# Hoja_Micro.net
KiCad netlist of a schematic drawn in Altium Designer
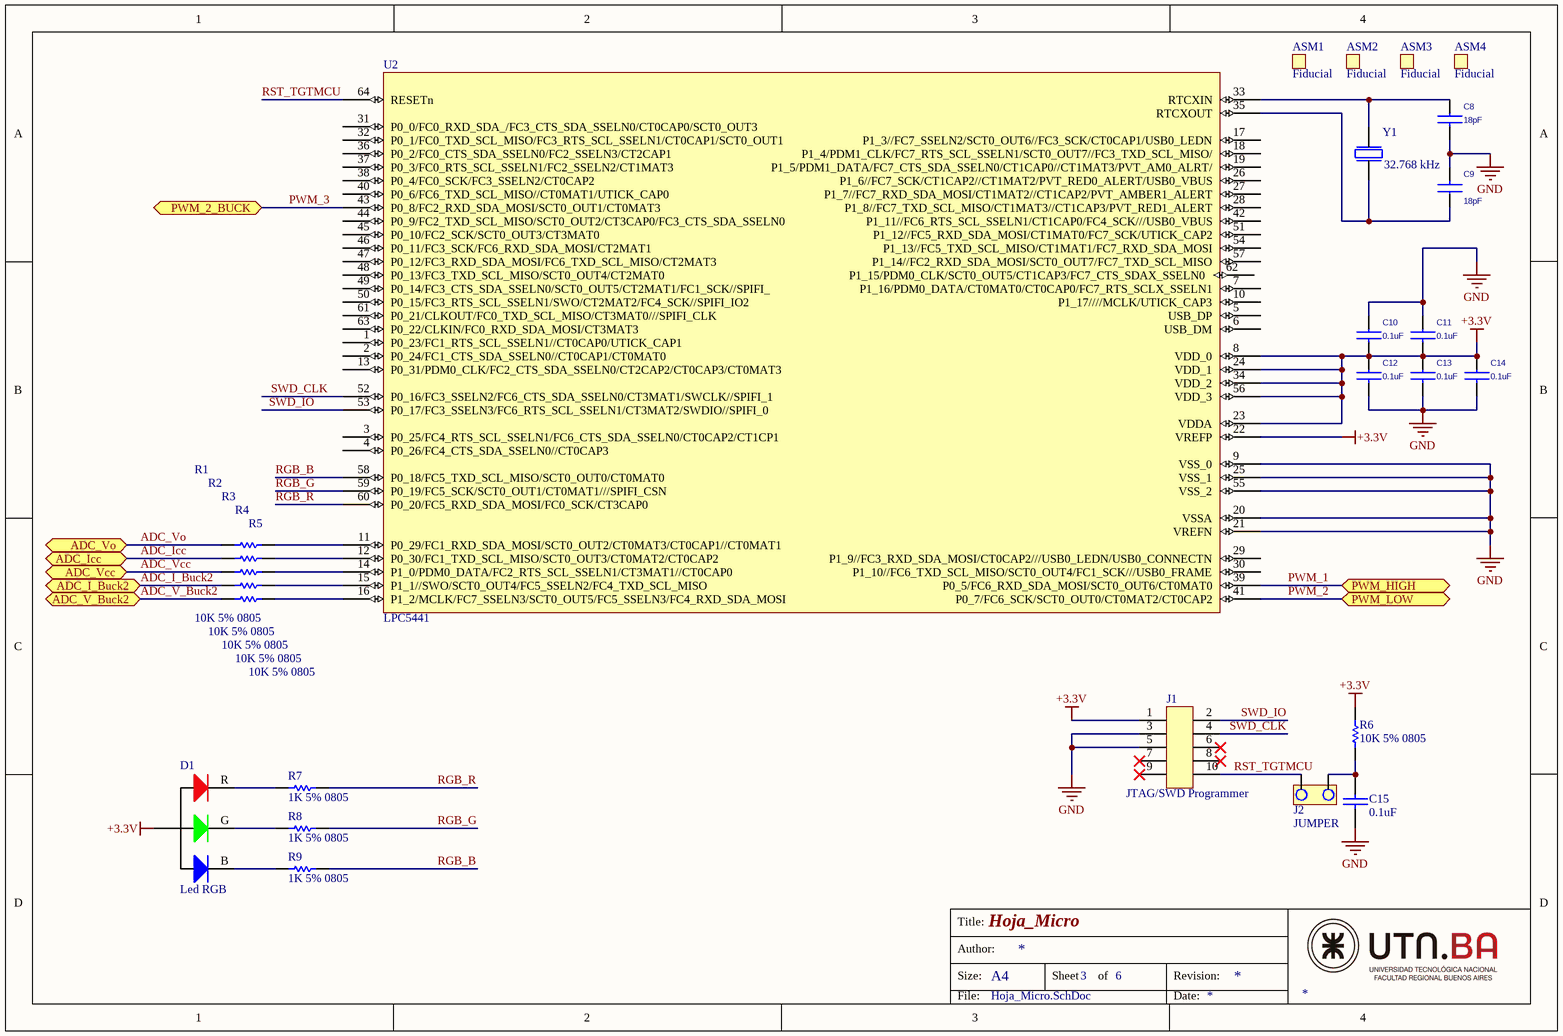
[diagram p0: Hoja_Micro.SchDoc]

(export (version "E")
  (design (tool "Eeschema 10.0.6"))
  (components
    (comp (ref "ASM1")
      (value "Fiducial")
      (footprint "Fiducial")
      (description "Fiducial Mark for PCB Asembly on Pick N' Place")
      (libsource (lib "Libreria_Casera") (part "Fiducial"))
    )
    (comp (ref "ASM2")
      (value "Fiducial")
      (footprint "Fiducial")
      (description "Fiducial Mark for PCB Asembly on Pick N' Place")
      (libsource (lib "Libreria_Casera") (part "Fiducial"))
    )
    (comp (ref "ASM3")
      (value "Fiducial")
      (footprint "Fiducial")
      (description "Fiducial Mark for PCB Asembly on Pick N' Place")
      (libsource (lib "Libreria_Casera") (part "Fiducial"))
    )
    (comp (ref "ASM4")
      (value "Fiducial")
      (footprint "Fiducial")
      (description "Fiducial Mark for PCB Asembly on Pick N' Place")
      (libsource (lib "Libreria_Casera") (part "Fiducial"))
    )
    (comp (ref "C8")
      (value "18pF")
      (footprint "0805")
      (description "CAP CER 0.1UF X7R 0805")
      (libsource (lib "*") (part "CAPACITOR NON-POL"))
    )
    (comp (ref "C9")
      (value "18pF")
      (footprint "0805")
      (description "CAP CER 0.1UF X7R 0805")
      (libsource (lib "*") (part "CAPACITOR NON-POL"))
    )
    (comp (ref "C10")
      (value "0.1uF")
      (footprint "0805")
      (description "CAP CER 0.1UF X7R 0805")
      (libsource (lib "*") (part "CAP NP"))
    )
    (comp (ref "C11")
      (value "0.1uF")
      (footprint "0805")
      (description "CAP CER 0.1UF X7R 0805")
      (libsource (lib "*") (part "CAP NP"))
    )
    (comp (ref "C12")
      (value "0.1uF")
      (footprint "0805")
      (description "CAP CER 0.1UF X7R 0805")
      (libsource (lib "*") (part "CAP NP"))
    )
    (comp (ref "C13")
      (value "0.1uF")
      (footprint "0805")
      (description "CAP CER 0.1UF X7R 0805")
      (libsource (lib "*") (part "CAP NP"))
    )
    (comp (ref "C14")
      (value "0.1uF")
      (footprint "0805")
      (description "CAP CER 0.1UF X7R 0805")
      (libsource (lib "*") (part "CAP NP"))
    )
    (comp (ref "C15")
      (value "0.1uF")
      (footprint "0805")
      (description "CAP CER 0.1UF X7R 0805")
      (libsource (lib "Libreria_Casera") (part "CAP"))
    )
    (comp (ref "D1")
      (value "Led RGB")
      (footprint "4-plcc")
      (description "CREE LED P/N: CLV1L-FKB-CHMMQEHBB7673673CT-ND\r\nCREE LED P/N: CLMVC-FKA-CL1D1L71BB7C3C3CT-ND")
      (libsource (lib "FRDM-KL46Z") (part "LED_RGB"))
    )
    (comp (ref "J1")
      (value "JTAG/SWD Programmer")
      (footprint "FTSH-105-01-XXX-DV-K")
      (description "CONN HEADER 10POS DUAL .05\" SMD -> FTSH-105-01-F-DV-K")
      (libsource (lib "FRDM-KL46Z") (part "JTAG"))
    )
    (comp (ref "J2") (value "JUMPER") (footprint "JUMPER2") (libsource (lib "LIBEBAL") (part "JUMPER")))
    (comp (ref "R1")
      (value "10K 5% 0805")
      (footprint "0805")
      (libsource (lib "Libreria_Casera") (part "RES"))
    )
    (comp (ref "R2")
      (value "10K 5% 0805")
      (footprint "0805")
      (libsource (lib "Libreria_Casera") (part "RES"))
    )
    (comp (ref "R3")
      (value "10K 5% 0805")
      (footprint "0805")
      (libsource (lib "Libreria_Casera") (part "RES"))
    )
    (comp (ref "R4")
      (value "10K 5% 0805")
      (footprint "0805")
      (libsource (lib "Libreria_Casera") (part "RES"))
    )
    (comp (ref "R5")
      (value "10K 5% 0805")
      (footprint "0805")
      (libsource (lib "Libreria_Casera") (part "RES"))
    )
    (comp (ref "R6")
      (value "10K 5% 0805")
      (footprint "0805")
      (description "RES SMD 10K OHM 5% 1/8W 0805")
      (libsource (lib "Libreria_Casera") (part "RES"))
    )
    (comp (ref "R7") (value "1K 5% 0805") (footprint "0805") (libsource (lib "Libreria_Casera") (part "RES")))
    (comp (ref "R8") (value "1K 5% 0805") (footprint "0805") (libsource (lib "Libreria_Casera") (part "RES")))
    (comp (ref "R9") (value "1K 5% 0805") (footprint "0805") (libsource (lib "Libreria_Casera") (part "RES")))
    (comp (ref "U2")
      (value "LPC5441")
      (footprint "LQFP64")
      (libsource (lib "Libreria_Casera") (part "LPC5441"))
    )
    (comp (ref "Y1")
      (value "32.768 kHz")
      (footprint "ABS07_Xtal")
      (description "XTAL ABS07 by ABRACON LLC")
      (libsource (lib "Libreria_Casera") (part "XTAL ABS07"))
    )
  )
  (nets
    (net (code "1") (name "+3.3V") (class "Default")
      (node (ref "C10") (pin "2") (pinfunction "2_2") (pintype "passive"))
      (node (ref "C11") (pin "2") (pinfunction "2_2") (pintype "passive"))
      (node (ref "C12") (pin "1") (pinfunction "1_1") (pintype "passive"))
      (node (ref "C13") (pin "1") (pinfunction "1_1") (pintype "passive"))
      (node (ref "C14") (pin "1") (pinfunction "1_1") (pintype "passive"))
      (node (ref "D1") (pin "A") (pinfunction "20_A") (pintype "passive"))
      (node (ref "J1") (pin "1") (pinfunction "36_1") (pintype "passive"))
      (node (ref "R6") (pin "2") (pinfunction "2_2") (pintype "passive"))
      (node (ref "U2") (pin "22") (pinfunction "VREFP_22") (pintype "bidirectional"))
      (node (ref "U2") (pin "23") (pinfunction "VDDA_23") (pintype "bidirectional"))
      (node (ref "U2") (pin "24") (pinfunction "VDD_1_24") (pintype "bidirectional"))
      (node (ref "U2") (pin "34") (pinfunction "VDD_2_34") (pintype "bidirectional"))
      (node (ref "U2") (pin "56") (pinfunction "VDD_3_56") (pintype "bidirectional"))
      (node (ref "U2") (pin "8") (pinfunction "VDD_0_8") (pintype "bidirectional"))
    )
    (net (code "2") (name "/ADC_I_Buck2") (class "Default")
      (node (ref "R4") (pin "2") (pinfunction "2_2") (pintype "passive"))
    )
    (net (code "3") (name "/ADC_Icc") (class "Default")
      (node (ref "R2") (pin "2") (pinfunction "2_2") (pintype "passive"))
    )
    (net (code "4") (name "/ADC_V_Buck2") (class "Default")
      (node (ref "R5") (pin "2") (pinfunction "2_2") (pintype "passive"))
    )
    (net (code "5") (name "/ADC_Vcc") (class "Default")
      (node (ref "R3") (pin "2") (pinfunction "2_2") (pintype "passive"))
    )
    (net (code "6") (name "/ADC_Vo") (class "Default")
      (node (ref "R1") (pin "2") (pinfunction "2_2") (pintype "passive"))
    )
    (net (code "7") (name "/PWM_1") (class "Default")
      (node (ref "U2") (pin "39") (pinfunction "P0_5/FC6_RXD_SDA_MOSI/SCT0_OUT6/CT0MAT0_39") (pintype "bidirectional"))
    )
    (net (code "8") (name "/PWM_2") (class "Default")
      (node (ref "U2") (pin "41") (pinfunction "P0_7/FC6_SCK/SCT0_OUT0/CT0MAT2/CT0CAP2_41") (pintype "bidirectional"))
    )
    (net (code "9") (name "/PWM_3") (class "Default")
      (node (ref "U2") (pin "43") (pinfunction "P0_8/FC2_RXD_SDA_MOSI/SCT0_OUT1/CT0MAT3_43") (pintype "bidirectional"))
    )
    (net (code "10") (name "/RGB_B") (class "Default")
      (node (ref "R9") (pin "1") (pinfunction "1_1") (pintype "passive"))
      (node (ref "U2") (pin "58") (pinfunction "P0_18/FC5_TXD_SCL_MISO/SCT0_OUT0/CT0MAT0_58") (pintype "bidirectional"))
    )
    (net (code "11") (name "/RGB_G") (class "Default")
      (node (ref "R8") (pin "1") (pinfunction "1_1") (pintype "passive"))
      (node (ref "U2") (pin "59") (pinfunction "P0_19/FC5_SCK/SCT0_OUT1/CT0MAT1///SPIFI_CSN_59") (pintype "bidirectional"))
    )
    (net (code "12") (name "/RGB_R") (class "Default")
      (node (ref "R7") (pin "1") (pinfunction "1_1") (pintype "passive"))
      (node (ref "U2") (pin "60") (pinfunction "P0_20/FC5_RXD_SDA_MOSI/FC0_SCK/CT3CAP0_60") (pintype "bidirectional"))
    )
    (net (code "13") (name "/RST_TGTMCU") (class "Default")
      (node (ref "J1") (pin "10") (pinfunction "41_10") (pintype "passive"))
      (node (ref "J2") (pin "1") (pinfunction "1_1") (pintype "passive"))
      (node (ref "U2") (pin "64") (pinfunction "RESETn_64") (pintype "bidirectional"))
    )
    (net (code "14") (name "/SWD_CLK") (class "Default")
      (node (ref "J1") (pin "4") (pinfunction "44_4") (pintype "passive"))
      (node (ref "U2") (pin "52") (pinfunction "P0_16/FC3_SSELN2/FC6_CTS_SDA_SSELN0/CT3MAT1/SWCLK//SPIFI_1_52") (pintype "bidirectional"))
    )
    (net (code "15") (name "/SWD_IO") (class "Default")
      (node (ref "J1") (pin "2") (pinfunction "45_2") (pintype "passive"))
      (node (ref "U2") (pin "53") (pinfunction "P0_17/FC3_SSELN3/FC6_RTS_SCL_SSELN1/CT3MAT2/SWDIO//SPIFI_0_53") (pintype "bidirectional"))
    )
    (net (code "16") (name "GND") (class "Default")
      (node (ref "C10") (pin "1") (pinfunction "1_1") (pintype "passive"))
      (node (ref "C11") (pin "1") (pinfunction "1_1") (pintype "passive"))
      (node (ref "C12") (pin "2") (pinfunction "2_2") (pintype "passive"))
      (node (ref "C13") (pin "2") (pinfunction "2_2") (pintype "passive"))
      (node (ref "C14") (pin "2") (pinfunction "2_2") (pintype "passive"))
      (node (ref "C15") (pin "2") (pinfunction "2_2") (pintype "passive"))
      (node (ref "C8") (pin "2") (pinfunction "2_2") (pintype "passive"))
      (node (ref "C9") (pin "2") (pinfunction "2_2") (pintype "passive"))
      (node (ref "J1") (pin "3") (pinfunction "37_3") (pintype "passive"))
      (node (ref "J1") (pin "5") (pinfunction "38_5") (pintype "passive"))
      (node (ref "U2") (pin "20") (pinfunction "VSSA_20") (pintype "bidirectional"))
      (node (ref "U2") (pin "21") (pinfunction "VREFN_21") (pintype "bidirectional"))
      (node (ref "U2") (pin "25") (pinfunction "VSS_1_25") (pintype "bidirectional"))
      (node (ref "U2") (pin "55") (pinfunction "VSS_2_55") (pintype "bidirectional"))
      (node (ref "U2") (pin "9") (pinfunction "VSS_0_9") (pintype "bidirectional"))
    )
    (net (code "17") (name "Net-(C15-Pad1)") (class "Default")
      (node (ref "C15") (pin "1") (pinfunction "1_1") (pintype "passive"))
      (node (ref "J2") (pin "2") (pinfunction "2_2") (pintype "passive"))
      (node (ref "R6") (pin "1") (pinfunction "1_1") (pintype "passive"))
    )
    (net (code "18") (name "Net-(D1-17)") (class "Default")
      (node (ref "D1") (pin "R") (pinfunction "17_R") (pintype "passive"))
      (node (ref "R7") (pin "2") (pinfunction "2_2") (pintype "passive"))
    )
    (net (code "19") (name "Net-(D1-18)") (class "Default")
      (node (ref "D1") (pin "G") (pinfunction "18_G") (pintype "passive"))
      (node (ref "R8") (pin "2") (pinfunction "2_2") (pintype "passive"))
    )
    (net (code "20") (name "Net-(D1-19)") (class "Default")
      (node (ref "D1") (pin "B") (pinfunction "19_B") (pintype "passive"))
      (node (ref "R9") (pin "2") (pinfunction "2_2") (pintype "passive"))
    )
    (net (code "21") (name "Net-(U2-P0_29{slash}FC1_RXD_SDA_MOSI{slash}SCT0_OUT2{slash}CT0MAT3{slash}CT0CAP1{slash}{slash}CT0MAT1)") (class "Default")
      (node (ref "R1") (pin "1") (pinfunction "1_1") (pintype "passive"))
      (node (ref "U2") (pin "11") (pinfunction "P0_29/FC1_RXD_SDA_MOSI/SCT0_OUT2/CT0MAT3/CT0CAP1//CT0MAT1_11") (pintype "bidirectional"))
    )
    (net (code "22") (name "Net-(U2-P0_30{slash}FC1_TXD_SCL_MISO{slash}SCT0_OUT3{slash}CT0MAT2{slash}CT0CAP2)") (class "Default")
      (node (ref "R2") (pin "1") (pinfunction "1_1") (pintype "passive"))
      (node (ref "U2") (pin "12") (pinfunction "P0_30/FC1_TXD_SCL_MISO/SCT0_OUT3/CT0MAT2/CT0CAP2_12") (pintype "bidirectional"))
    )
    (net (code "23") (name "Net-(U2-P1_0{slash}PDM0_DATA{slash}FC2_RTS_SCL_SSELN1{slash}CT3MAT1{slash}{slash}CT0CAP0)") (class "Default")
      (node (ref "R3") (pin "1") (pinfunction "1_1") (pintype "passive"))
      (node (ref "U2") (pin "14") (pinfunction "P1_0/PDM0_DATA/FC2_RTS_SCL_SSELN1/CT3MAT1//CT0CAP0_14") (pintype "bidirectional"))
    )
    (net (code "24") (name "Net-(U2-P1_1{slash}{slash}SWO{slash}SCT0_OUT4{slash}FC5_SSELN2{slash}FC4_TXD_SCL_MISO)") (class "Default")
      (node (ref "R4") (pin "1") (pinfunction "1_1") (pintype "passive"))
      (node (ref "U2") (pin "15") (pinfunction "P1_1//SWO/SCT0_OUT4/FC5_SSELN2/FC4_TXD_SCL_MISO_15") (pintype "bidirectional"))
    )
    (net (code "25") (name "Net-(U2-P1_2{slash}MCLK{slash}FC7_SSELN3{slash}SCT0_OUT5{slash}FC5_SSELN3{slash}FC4_RXD_SDA_MOSI)") (class "Default")
      (node (ref "R5") (pin "1") (pinfunction "1_1") (pintype "passive"))
      (node (ref "U2") (pin "16") (pinfunction "P1_2/MCLK/FC7_SSELN3/SCT0_OUT5/FC5_SSELN3/FC4_RXD_SDA_MOSI_16") (pintype "bidirectional"))
    )
    (net (code "26") (name "Net-(U2-RTCXIN)") (class "Default")
      (node (ref "C8") (pin "1") (pinfunction "1_1") (pintype "passive"))
      (node (ref "U2") (pin "33") (pinfunction "RTCXIN_33") (pintype "bidirectional"))
      (node (ref "Y1") (pin "2") (pinfunction "35_2") (pintype "passive"))
    )
    (net (code "27") (name "Net-(U2-RTCXOUT)") (class "Default")
      (node (ref "C9") (pin "1") (pinfunction "1_1") (pintype "passive"))
      (node (ref "U2") (pin "35") (pinfunction "RTCXOUT_35") (pintype "bidirectional"))
      (node (ref "Y1") (pin "1") (pinfunction "34_1") (pintype "passive"))
    )
    (net (code "28") (name "unconnected-(J1-39-Pad7)") (class "Default")
      (node (ref "J1") (pin "7") (pinfunction "39_7") (pintype "passive+no_connect"))
    )
    (net (code "29") (name "unconnected-(J1-40-Pad9)") (class "Default")
      (node (ref "J1") (pin "9") (pinfunction "40_9") (pintype "passive+no_connect"))
    )
    (net (code "30") (name "unconnected-(J1-42-Pad8)") (class "Default")
      (node (ref "J1") (pin "8") (pinfunction "42_8") (pintype "passive+no_connect"))
    )
    (net (code "31") (name "unconnected-(J1-43-Pad6)") (class "Default")
      (node (ref "J1") (pin "6") (pinfunction "43_6") (pintype "passive+no_connect"))
    )
    (net (code "32") (name "unconnected-(U2-P0_0{slash}FC0_RXD_SDA_{slash}FC3_CTS_SDA_SSELN0{slash}CT0CAP0{slash}SCT0_OUT3-Pad31)") (class "Default")
      (node (ref "U2") (pin "31") (pinfunction "P0_0/FC0_RXD_SDA_/FC3_CTS_SDA_SSELN0/CT0CAP0/SCT0_OUT3_31") (pintype "bidirectional"))
    )
    (net (code "33") (name "unconnected-(U2-P0_1{slash}FC0_TXD_SCL_MISO{slash}FC3_RTS_SCL_SSELN1{slash}CT0CAP1{slash}SCT0_OUT1-Pad32)") (class "Default")
      (node (ref "U2") (pin "32") (pinfunction "P0_1/FC0_TXD_SCL_MISO/FC3_RTS_SCL_SSELN1/CT0CAP1/SCT0_OUT1_32") (pintype "bidirectional"))
    )
    (net (code "34") (name "unconnected-(U2-P0_2{slash}FC0_CTS_SDA_SSELN0{slash}FC2_SSELN3{slash}CT2CAP1-Pad36)") (class "Default")
      (node (ref "U2") (pin "36") (pinfunction "P0_2/FC0_CTS_SDA_SSELN0/FC2_SSELN3/CT2CAP1_36") (pintype "bidirectional"))
    )
    (net (code "35") (name "unconnected-(U2-P0_3{slash}FC0_RTS_SCL_SSELN1{slash}FC2_SSELN2{slash}CT1MAT3-Pad37)") (class "Default")
      (node (ref "U2") (pin "37") (pinfunction "P0_3/FC0_RTS_SCL_SSELN1/FC2_SSELN2/CT1MAT3_37") (pintype "bidirectional"))
    )
    (net (code "36") (name "unconnected-(U2-P0_4{slash}FC0_SCK{slash}FC3_SSELN2{slash}CT0CAP2-Pad38)") (class "Default")
      (node (ref "U2") (pin "38") (pinfunction "P0_4/FC0_SCK/FC3_SSELN2/CT0CAP2_38") (pintype "bidirectional"))
    )
    (net (code "37") (name "unconnected-(U2-P0_6{slash}FC6_TXD_SCL_MISO{slash}{slash}CT0MAT1{slash}UTICK_CAP0-Pad40)") (class "Default")
      (node (ref "U2") (pin "40") (pinfunction "P0_6/FC6_TXD_SCL_MISO//CT0MAT1/UTICK_CAP0_40") (pintype "bidirectional"))
    )
    (net (code "38") (name "unconnected-(U2-P0_9{slash}FC2_TXD_SCL_MISO{slash}SCT0_OUT2{slash}CT3CAP0{slash}FC3_CTS_SDA_SSELN0-Pad44)") (class "Default")
      (node (ref "U2") (pin "44") (pinfunction "P0_9/FC2_TXD_SCL_MISO/SCT0_OUT2/CT3CAP0/FC3_CTS_SDA_SSELN0_44") (pintype "bidirectional"))
    )
    (net (code "39") (name "unconnected-(U2-P0_10{slash}FC2_SCK{slash}SCT0_OUT3{slash}CT3MAT0-Pad45)") (class "Default")
      (node (ref "U2") (pin "45") (pinfunction "P0_10/FC2_SCK/SCT0_OUT3/CT3MAT0_45") (pintype "bidirectional"))
    )
    (net (code "40") (name "unconnected-(U2-P0_11{slash}FC3_SCK{slash}FC6_RXD_SDA_MOSI{slash}CT2MAT1-Pad46)") (class "Default")
      (node (ref "U2") (pin "46") (pinfunction "P0_11/FC3_SCK/FC6_RXD_SDA_MOSI/CT2MAT1_46") (pintype "bidirectional"))
    )
    (net (code "41") (name "unconnected-(U2-P0_12{slash}FC3_RXD_SDA_MOSI{slash}FC6_TXD_SCL_MISO{slash}CT2MAT3-Pad47)") (class "Default")
      (node (ref "U2") (pin "47") (pinfunction "P0_12/FC3_RXD_SDA_MOSI/FC6_TXD_SCL_MISO/CT2MAT3_47") (pintype "bidirectional"))
    )
    (net (code "42") (name "unconnected-(U2-P0_13{slash}FC3_TXD_SCL_MISO{slash}SCT0_OUT4{slash}CT2MAT0-Pad48)") (class "Default")
      (node (ref "U2") (pin "48") (pinfunction "P0_13/FC3_TXD_SCL_MISO/SCT0_OUT4/CT2MAT0_48") (pintype "bidirectional"))
    )
    (net (code "43") (name "unconnected-(U2-P0_14{slash}FC3_CTS_SDA_SSELN0{slash}SCT0_OUT5{slash}CT2MAT1{slash}FC1_SCK{slash}{slash}SPIFI_-Pad49)") (class "Default")
      (node (ref "U2") (pin "49") (pinfunction "P0_14/FC3_CTS_SDA_SSELN0/SCT0_OUT5/CT2MAT1/FC1_SCK//SPIFI__49") (pintype "bidirectional"))
    )
    (net (code "44") (name "unconnected-(U2-P0_15{slash}FC3_RTS_SCL_SSELN1{slash}SWO{slash}CT2MAT2{slash}FC4_SCK{slash}{slash}SPIFI_IO2-Pad50)") (class "Default")
      (node (ref "U2") (pin "50") (pinfunction "P0_15/FC3_RTS_SCL_SSELN1/SWO/CT2MAT2/FC4_SCK//SPIFI_IO2_50") (pintype "bidirectional"))
    )
    (net (code "45") (name "unconnected-(U2-P0_21{slash}CLKOUT{slash}FC0_TXD_SCL_MISO{slash}CT3MAT0{slash}{slash}{slash}SPIFI_CLK-Pad61)") (class "Default")
      (node (ref "U2") (pin "61") (pinfunction "P0_21/CLKOUT/FC0_TXD_SCL_MISO/CT3MAT0///SPIFI_CLK_61") (pintype "bidirectional"))
    )
    (net (code "46") (name "unconnected-(U2-P0_22{slash}CLKIN{slash}FC0_RXD_SDA_MOSI{slash}CT3MAT3-Pad63)") (class "Default")
      (node (ref "U2") (pin "63") (pinfunction "P0_22/CLKIN/FC0_RXD_SDA_MOSI/CT3MAT3_63") (pintype "bidirectional"))
    )
    (net (code "47") (name "unconnected-(U2-P0_23{slash}FC1_RTS_SCL_SSELN1{slash}{slash}CT0CAP0{slash}UTICK_CAP1-Pad1)") (class "Default")
      (node (ref "U2") (pin "1") (pinfunction "P0_23/FC1_RTS_SCL_SSELN1//CT0CAP0/UTICK_CAP1_1") (pintype "bidirectional"))
    )
    (net (code "48") (name "unconnected-(U2-P0_24{slash}FC1_CTS_SDA_SSELN0{slash}{slash}CT0CAP1{slash}CT0MAT0-Pad2)") (class "Default")
      (node (ref "U2") (pin "2") (pinfunction "P0_24/FC1_CTS_SDA_SSELN0//CT0CAP1/CT0MAT0_2") (pintype "bidirectional"))
    )
    (net (code "49") (name "unconnected-(U2-P0_25{slash}FC4_RTS_SCL_SSELN1{slash}FC6_CTS_SDA_SSELN0{slash}CT0CAP2{slash}CT1CP1-Pad3)") (class "Default")
      (node (ref "U2") (pin "3") (pinfunction "P0_25/FC4_RTS_SCL_SSELN1/FC6_CTS_SDA_SSELN0/CT0CAP2/CT1CP1_3") (pintype "bidirectional"))
    )
    (net (code "50") (name "unconnected-(U2-P0_26{slash}FC4_CTS_SDA_SSELN0{slash}{slash}CT0CAP3-Pad4)") (class "Default")
      (node (ref "U2") (pin "4") (pinfunction "P0_26/FC4_CTS_SDA_SSELN0//CT0CAP3_4") (pintype "bidirectional"))
    )
    (net (code "51") (name "unconnected-(U2-P0_31{slash}PDM0_CLK{slash}FC2_CTS_SDA_SSELN0{slash}CT2CAP2{slash}CT0CAP3{slash}CT0MAT3-Pad13)") (class "Default")
      (node (ref "U2") (pin "13") (pinfunction "P0_31/PDM0_CLK/FC2_CTS_SDA_SSELN0/CT2CAP2/CT0CAP3/CT0MAT3_13") (pintype "bidirectional"))
    )
    (net (code "52") (name "unconnected-(U2-P1_3{slash}{slash}FC7_SSELN2{slash}SCT0_OUT6{slash}{slash}FC3_SCK{slash}CT0CAP1{slash}USB0_LEDN-Pad17)") (class "Default")
      (node (ref "U2") (pin "17") (pinfunction "P1_3//FC7_SSELN2/SCT0_OUT6//FC3_SCK/CT0CAP1/USB0_LEDN_17") (pintype "bidirectional"))
    )
    (net (code "53") (name "unconnected-(U2-P1_4{slash}PDM1_CLK{slash}FC7_RTS_SCL_SSELN1{slash}SCT0_OUT7{slash}{slash}FC3_TXD_SCL_MISO{slash}-Pad18)") (class "Default")
      (node (ref "U2") (pin "18") (pinfunction "P1_4/PDM1_CLK/FC7_RTS_SCL_SSELN1/SCT0_OUT7//FC3_TXD_SCL_MISO/_18") (pintype "bidirectional"))
    )
    (net (code "54") (name "unconnected-(U2-P1_5{slash}PDM1_DATA{slash}FC7_CTS_SDA_SSELN0{slash}CT1CAP0{slash}{slash}CT1MAT3{slash}PVT_AM0_ALRT{slash}-Pad19)") (class "Default")
      (node (ref "U2") (pin "19") (pinfunction "P1_5/PDM1_DATA/FC7_CTS_SDA_SSELN0/CT1CAP0//CT1MAT3/PVT_AM0_ALRT/_19") (pintype "bidirectional"))
    )
    (net (code "55") (name "unconnected-(U2-P1_6{slash}{slash}FC7_SCK{slash}CT1CAP2{slash}{slash}CT1MAT2{slash}PVT_RED0_ALERT{slash}USB0_VBUS-Pad26)") (class "Default")
      (node (ref "U2") (pin "26") (pinfunction "P1_6//FC7_SCK/CT1CAP2//CT1MAT2/PVT_RED0_ALERT/USB0_VBUS_26") (pintype "bidirectional"))
    )
    (net (code "56") (name "unconnected-(U2-P1_7{slash}{slash}FC7_RXD_SDA_MOSI{slash}CT1MAT2{slash}{slash}CT1CAP2{slash}PVT_AMBER1_ALERT-Pad27)") (class "Default")
      (node (ref "U2") (pin "27") (pinfunction "P1_7//FC7_RXD_SDA_MOSI/CT1MAT2//CT1CAP2/PVT_AMBER1_ALERT_27") (pintype "bidirectional"))
    )
    (net (code "57") (name "unconnected-(U2-P1_8{slash}{slash}FC7_TXD_SCL_MISO{slash}CT1MAT3{slash}{slash}CT1CAP3{slash}PVT_RED1_ALERT-Pad28)") (class "Default")
      (node (ref "U2") (pin "28") (pinfunction "P1_8//FC7_TXD_SCL_MISO/CT1MAT3//CT1CAP3/PVT_RED1_ALERT_28") (pintype "bidirectional"))
    )
    (net (code "58") (name "unconnected-(U2-P1_9{slash}{slash}FC3_RXD_SDA_MOSI{slash}CT0CAP2{slash}{slash}{slash}USB0_LEDN{slash}USB0_CONNECTN-Pad29)") (class "Default")
      (node (ref "U2") (pin "29") (pinfunction "P1_9//FC3_RXD_SDA_MOSI/CT0CAP2///USB0_LEDN/USB0_CONNECTN_29") (pintype "bidirectional"))
    )
    (net (code "59") (name "unconnected-(U2-P1_10{slash}{slash}FC6_TXD_SCL_MISO{slash}SCT0_OUT4{slash}FC1_SCK{slash}{slash}{slash}USB0_FRAME-Pad30)") (class "Default")
      (node (ref "U2") (pin "30") (pinfunction "P1_10//FC6_TXD_SCL_MISO/SCT0_OUT4/FC1_SCK///USB0_FRAME_30") (pintype "bidirectional"))
    )
    (net (code "60") (name "unconnected-(U2-P1_11{slash}{slash}FC6_RTS_SCL_SSELN1{slash}CT1CAP0{slash}FC4_SCK{slash}{slash}{slash}USB0_VBUS-Pad42)") (class "Default")
      (node (ref "U2") (pin "42") (pinfunction "P1_11//FC6_RTS_SCL_SSELN1/CT1CAP0/FC4_SCK///USB0_VBUS_42") (pintype "bidirectional"))
    )
    (net (code "61") (name "unconnected-(U2-P1_12{slash}{slash}FC5_RXD_SDA_MOSI{slash}CT1MAT0{slash}FC7_SCK{slash}UTICK_CAP2-Pad51)") (class "Default")
      (node (ref "U2") (pin "51") (pinfunction "P1_12//FC5_RXD_SDA_MOSI/CT1MAT0/FC7_SCK/UTICK_CAP2_51") (pintype "bidirectional"))
    )
    (net (code "62") (name "unconnected-(U2-P1_13{slash}{slash}FC5_TXD_SCL_MISO{slash}CT1MAT1{slash}FC7_RXD_SDA_MOSI-Pad54)") (class "Default")
      (node (ref "U2") (pin "54") (pinfunction "P1_13//FC5_TXD_SCL_MISO/CT1MAT1/FC7_RXD_SDA_MOSI_54") (pintype "bidirectional"))
    )
    (net (code "63") (name "unconnected-(U2-P1_14{slash}{slash}FC2_RXD_SDA_MOSI{slash}SCT0_OUT7{slash}FC7_TXD_SCL_MISO-Pad57)") (class "Default")
      (node (ref "U2") (pin "57") (pinfunction "P1_14//FC2_RXD_SDA_MOSI/SCT0_OUT7/FC7_TXD_SCL_MISO_57") (pintype "bidirectional"))
    )
    (net (code "64") (name "unconnected-(U2-P1_15{slash}PDM0_CLK{slash}SCT0_OUT5{slash}CT1CAP3{slash}FC7_CTS_SDAX_SSELN0-Pad62)") (class "Default")
      (node (ref "U2") (pin "62") (pinfunction "P1_15/PDM0_CLK/SCT0_OUT5/CT1CAP3/FC7_CTS_SDAX_SSELN0_62") (pintype "bidirectional"))
    )
    (net (code "65") (name "unconnected-(U2-P1_16{slash}PDM0_DATA{slash}CT0MAT0{slash}CT0CAP0{slash}FC7_RTS_SCLX_SSELN1-Pad7)") (class "Default")
      (node (ref "U2") (pin "7") (pinfunction "P1_16/PDM0_DATA/CT0MAT0/CT0CAP0/FC7_RTS_SCLX_SSELN1_7") (pintype "bidirectional"))
    )
    (net (code "66") (name "unconnected-(U2-P1_17{slash}{slash}{slash}{slash}MCLK{slash}UTICK_CAP3-Pad10)") (class "Default")
      (node (ref "U2") (pin "10") (pinfunction "P1_17////MCLK/UTICK_CAP3_10") (pintype "bidirectional"))
    )
    (net (code "67") (name "unconnected-(U2-USB_DM-Pad6)") (class "Default")
      (node (ref "U2") (pin "6") (pinfunction "USB_DM_6") (pintype "bidirectional"))
    )
    (net (code "68") (name "unconnected-(U2-USB_DP-Pad5)") (class "Default")
      (node (ref "U2") (pin "5") (pinfunction "USB_DP_5") (pintype "bidirectional"))
    )
  )
)
